# Digital_IO_Connector.net
KiCad netlist of a schematic drawn in Altium Designer
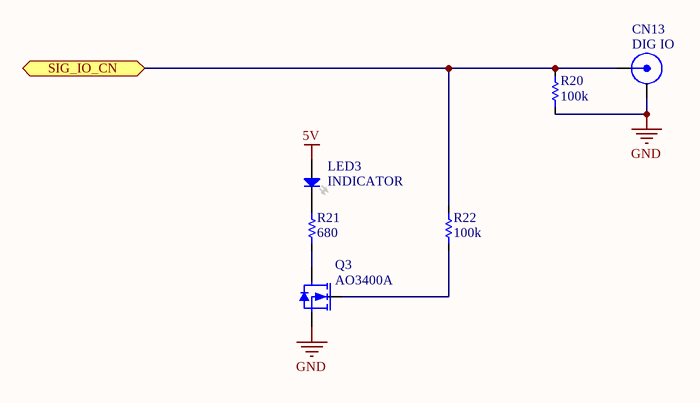
[diagram p0: Digital IO Connector.SchDoc]

(export (version "E")
  (design (tool "Eeschema 10.0.6"))
  (components
    (comp (ref "CN13")
      (value "DIG IO")
      (footprint "BNC-AMP-112515")
      (description "RF BNC Connector, Female, Board Mount, Solder Terminal, Jack")
      (fields (field (name "PARTNUMBER") "112515"))
      (libsource (lib "Sainsbury Wellcome Centre") (part "RF-Jack"))
    )
    (comp (ref "LED3")
      (value "INDICATOR")
      (footprint "LED_CHIP_0805")
      (description "White 0805 Light Emitting Diodes (LED) ROHS")
      (fields (field (name "PARTNUMBER") "KT-0805W"))
      (libsource (lib "Sainsbury Wellcome Centre") (part "LED-WHITE"))
    )
    (comp (ref "Q3")
      (value "AO3400A")
      (footprint "SOT23")
      (description "30V 5.7A 26.5mΩ@10V,5.7A 1.4W 1.5V@250uA 1 NChannel SOT-23-3L MOSFETs")
      (fields (field (name "PARTNUMBER") "AO3400A"))
      (libsource (lib "Sainsbury Wellcome Centre") (part "NMOS"))
    )
    (comp (ref "R20")
      (value "100k")
      (footprint "RES_CHIP_0603")
      (description "100mW Thick Film Resistors 75V ±100ppm/℃ ±1% 0603 Chip Resistor")
      (fields (field (name "PARTNUMBER") "0603WAF1003T5E") (field (name "TOLERANCE") "1%"))
      (libsource (lib "Sainsbury Wellcome Centre") (part "Res"))
    )
    (comp (ref "R21")
      (value "680")
      (footprint "RES_CHIP_0603")
      (description "100mW Thick Film Resistors 75V ±100ppm/℃ ±1% 0603 Chip Resistor")
      (fields (field (name "PARTNUMBER") "0603WAF6800T5E") (field (name "TOLERANCE") "1%"))
      (libsource (lib "Sainsbury Wellcome Centre") (part "Res"))
    )
    (comp (ref "R22")
      (value "100k")
      (footprint "RES_CHIP_0603")
      (description "100mW Thick Film Resistors 75V ±100ppm/℃ ±1% 0603 Chip Resistor")
      (fields (field (name "PARTNUMBER") "0603WAF1003T5E") (field (name "TOLERANCE") "1%"))
      (libsource (lib "Sainsbury Wellcome Centre") (part "Res"))
    )
  )
  (nets
    (net (code "1") (name "/SIG_IO_CN") (class "Default")
      (node (ref "CN13") (pin "1") (pinfunction "SIG_1") (pintype "passive"))
      (node (ref "R20") (pin "2") (pinfunction "2_2") (pintype "passive"))
      (node (ref "R22") (pin "2") (pinfunction "2_2") (pintype "passive"))
    )
    (net (code "2") (name "5V") (class "Default")
      (node (ref "LED3") (pin "2") (pinfunction "A_2") (pintype "passive"))
    )
    (net (code "3") (name "GND") (class "Default")
      (node (ref "CN13") (pin "2") (pinfunction "GND_2") (pintype "passive"))
      (node (ref "Q3") (pin "2") (pinfunction "S_2") (pintype "passive"))
      (node (ref "R20") (pin "1") (pinfunction "1_1") (pintype "passive"))
    )
    (net (code "4") (name "Net-(LED3-K)") (class "Default")
      (node (ref "LED3") (pin "1") (pinfunction "K_1") (pintype "passive"))
      (node (ref "R21") (pin "2") (pinfunction "2_2") (pintype "passive"))
    )
    (net (code "5") (name "Net-(Q3-D)") (class "Default")
      (node (ref "Q3") (pin "3") (pinfunction "D_3") (pintype "passive"))
      (node (ref "R21") (pin "1") (pinfunction "1_1") (pintype "passive"))
    )
    (net (code "6") (name "Net-(Q3-G)") (class "Default")
      (node (ref "Q3") (pin "1") (pinfunction "G_1") (pintype "passive"))
      (node (ref "R22") (pin "1") (pinfunction "1_1") (pintype "passive"))
    )
  )
)
